# ramanPi_powerControlBoard.net
KiCad netlist of a schematic drawn in EAGLE
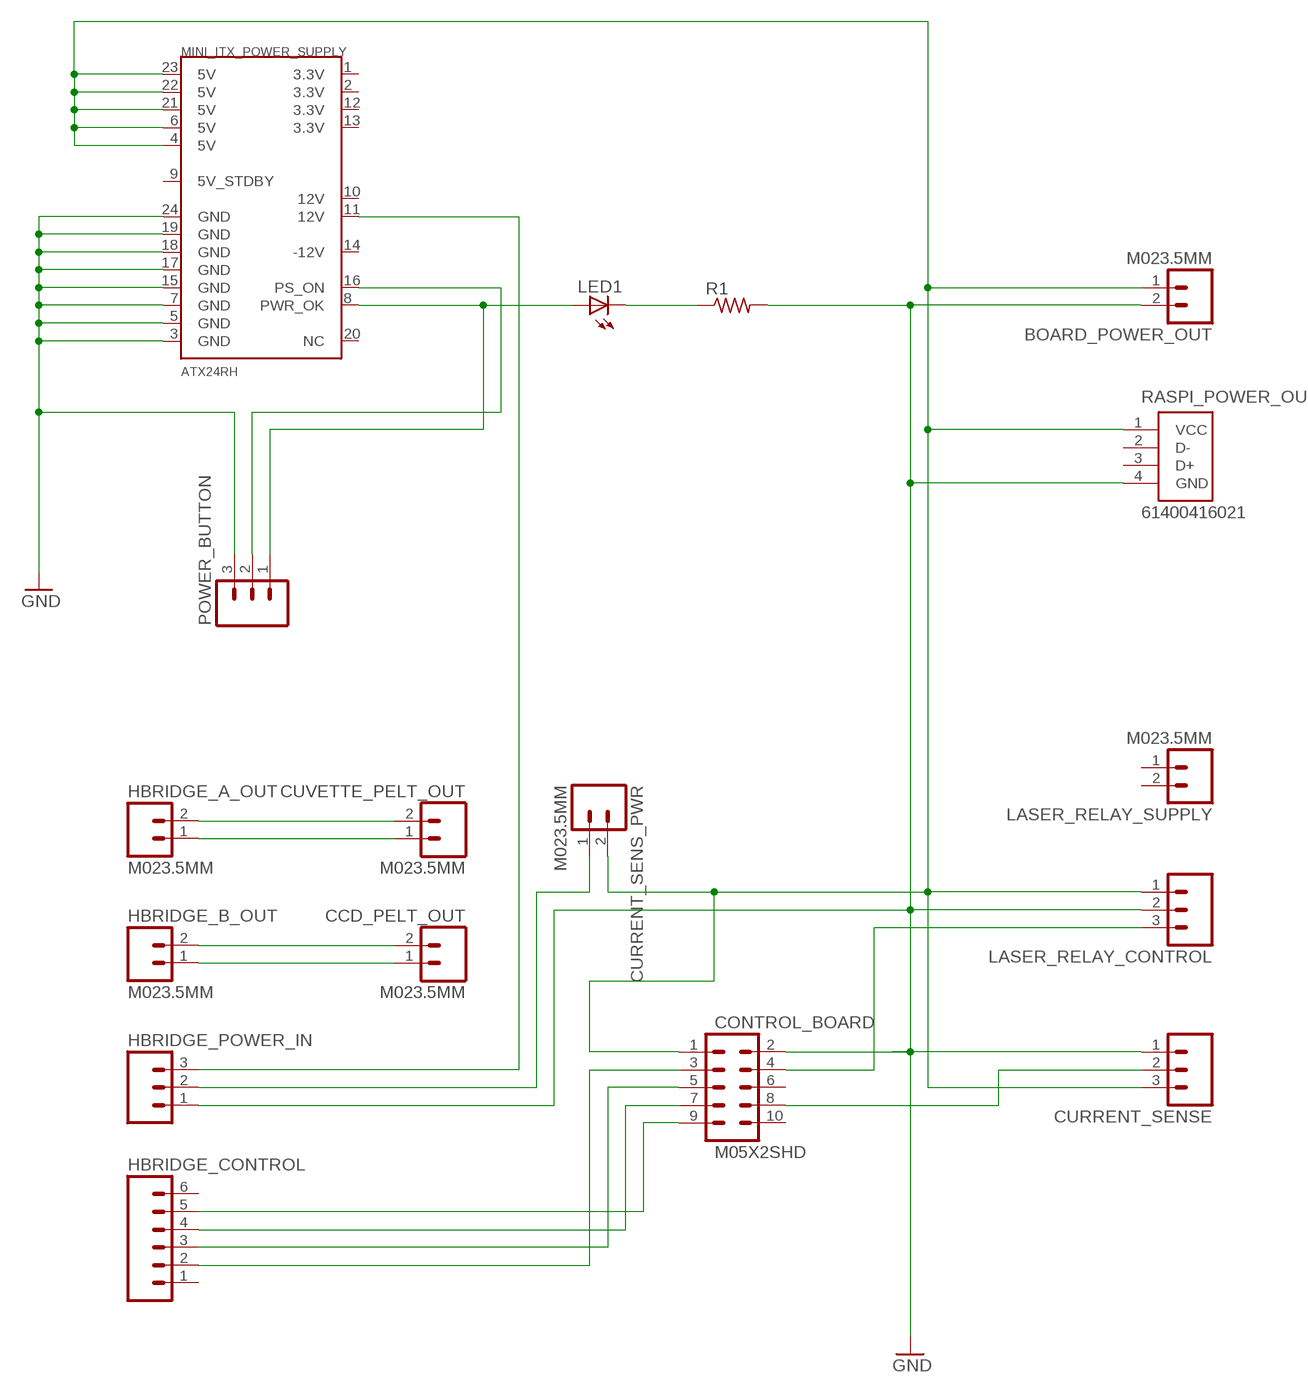
[diagram p0: schematic, sheet 1]

(export (version "E")
  (design (tool "Eeschema 10.0.6"))
  (components
    (comp (ref "BOARD_POWER_OUT")
      (value "M023.5MM")
      (footprint "eagle-import:SCREWTERMINAL-3.5MM-2")
      (libsource (lib "eagle-import") (part "M023.5MM"))
    )
    (comp (ref "CCD_PELT_OUT")
      (value "M023.5MM")
      (footprint "eagle-import:SCREWTERMINAL-3.5MM-2")
      (libsource (lib "eagle-import") (part "M023.5MM"))
    )
    (comp (ref "CONTROL_BOARD")
      (value "M05X2SHD")
      (footprint "eagle-import:2X5-SHROUDED")
      (libsource (lib "eagle-import") (part "M05X2SHD"))
    )
    (comp (ref "CURRENT_SENSE")
      (value "M03PTH")
      (footprint "eagle-import:1X03")
      (libsource (lib "eagle-import") (part "M03PTH"))
    )
    (comp (ref "CURRENT_SENS_PWR")
      (value "M023.5MM")
      (footprint "eagle-import:SCREWTERMINAL-3.5MM-2")
      (libsource (lib "eagle-import") (part "M023.5MM"))
    )
    (comp (ref "CUVETTE_PELT_OUT")
      (value "M023.5MM")
      (footprint "eagle-import:SCREWTERMINAL-3.5MM-2")
      (libsource (lib "eagle-import") (part "M023.5MM"))
    )
    (comp (ref "HBRIDGE_A_OUT")
      (value "M023.5MM")
      (footprint "eagle-import:SCREWTERMINAL-3.5MM-2")
      (libsource (lib "eagle-import") (part "M023.5MM"))
    )
    (comp (ref "HBRIDGE_B_OUT")
      (value "M023.5MM")
      (footprint "eagle-import:SCREWTERMINAL-3.5MM-2")
      (libsource (lib "eagle-import") (part "M023.5MM"))
    )
    (comp (ref "HBRIDGE_CONTROL")
      (value "M06SIP")
      (footprint "eagle-import:1X06")
      (libsource (lib "eagle-import") (part "M06SIP"))
    )
    (comp (ref "HBRIDGE_POWER_IN")
      (value "M03SCREW")
      (footprint "eagle-import:SCREWTERMINAL-3.5MM-3")
      (libsource (lib "eagle-import") (part "M03SCREW"))
    )
    (comp (ref "LASER_RELAY_CONTROL")
      (value "M03PTH")
      (footprint "eagle-import:1X03")
      (libsource (lib "eagle-import") (part "M03PTH"))
    )
    (comp (ref "LASER_RELAY_SUPPLY")
      (value "M023.5MM")
      (footprint "eagle-import:SCREWTERMINAL-3.5MM-2")
      (libsource (lib "eagle-import") (part "M023.5MM"))
    )
    (comp (ref "LED1")
      (value "LED5MM")
      (footprint "eagle-import:LED5MM")
      (libsource (lib "eagle-import") (part "LED5MM"))
    )
    (comp (ref "MINI_ITX_POWER_SUPPLY")
      (value "ATX24RH")
      (footprint "eagle-import:ATX24_RIGHT_ANGLE")
      (libsource (lib "eagle-import") (part "ATX24RH"))
    )
    (comp (ref "POWER_BUTTON")
      (value "M03JST-PTH-VERT")
      (footprint "eagle-import:JST-3-PTH-VERT")
      (libsource (lib "eagle-import") (part "M03JST-PTH-VERT"))
    )
    (comp (ref "R1")
      (value "R-US_M1206")
      (footprint "eagle-import:M1206")
      (libsource (lib "eagle-import") (part "R-US_M1206"))
    )
    (comp (ref "RASPI_POWER_OUT")
      (value "61400416021")
      (footprint "eagle-import:61400416021")
      (libsource (lib "eagle-import") (part "61400416021"))
    )
  )
  (nets
    (net (code "1") (name "GND") (class "Default")
      (node (ref "BOARD_POWER_OUT") (pin "2") (pinfunction "2_2") (pintype "passive"))
      (node (ref "CONTROL_BOARD") (pin "2") (pinfunction "2_2") (pintype "passive"))
      (node (ref "CURRENT_SENSE") (pin "1") (pinfunction "1_1") (pintype "passive"))
      (node (ref "HBRIDGE_POWER_IN") (pin "1") (pinfunction "1_1") (pintype "passive"))
      (node (ref "LASER_RELAY_CONTROL") (pin "2") (pinfunction "2_2") (pintype "passive"))
      (node (ref "MINI_ITX_POWER_SUPPLY") (pin "15") (pinfunction "GND_15") (pintype "bidirectional"))
      (node (ref "MINI_ITX_POWER_SUPPLY") (pin "17") (pinfunction "GND_17") (pintype "bidirectional"))
      (node (ref "MINI_ITX_POWER_SUPPLY") (pin "18") (pinfunction "GND_18") (pintype "bidirectional"))
      (node (ref "MINI_ITX_POWER_SUPPLY") (pin "19") (pinfunction "GND_19") (pintype "bidirectional"))
      (node (ref "MINI_ITX_POWER_SUPPLY") (pin "24") (pinfunction "GND_24") (pintype "bidirectional"))
      (node (ref "MINI_ITX_POWER_SUPPLY") (pin "3") (pinfunction "GND_3") (pintype "bidirectional"))
      (node (ref "MINI_ITX_POWER_SUPPLY") (pin "5") (pinfunction "GND_5") (pintype "bidirectional"))
      (node (ref "MINI_ITX_POWER_SUPPLY") (pin "7") (pinfunction "GND_7") (pintype "bidirectional"))
      (node (ref "POWER_BUTTON") (pin "3") (pinfunction "3_3") (pintype "passive"))
      (node (ref "R1") (pin "2") (pinfunction "2_2") (pintype "passive"))
      (node (ref "RASPI_POWER_OUT") (pin "4") (pinfunction "GND_4") (pintype "passive"))
    )
    (net (code "2") (name "Net-(CCD_PELT_OUT-Pad1)") (class "Default")
      (node (ref "CCD_PELT_OUT") (pin "1") (pinfunction "1_1") (pintype "passive"))
      (node (ref "HBRIDGE_B_OUT") (pin "1") (pinfunction "1_1") (pintype "passive"))
    )
    (net (code "3") (name "Net-(CCD_PELT_OUT-Pad2)") (class "Default")
      (node (ref "CCD_PELT_OUT") (pin "2") (pinfunction "2_2") (pintype "passive"))
      (node (ref "HBRIDGE_B_OUT") (pin "2") (pinfunction "2_2") (pintype "passive"))
    )
    (net (code "4") (name "Net-(CONTROL_BOARD-Pad3)") (class "Default")
      (node (ref "CONTROL_BOARD") (pin "3") (pinfunction "3_3") (pintype "passive"))
      (node (ref "HBRIDGE_CONTROL") (pin "2") (pinfunction "2_2") (pintype "passive"))
    )
    (net (code "5") (name "Net-(CONTROL_BOARD-Pad4)") (class "Default")
      (node (ref "CONTROL_BOARD") (pin "4") (pinfunction "4_4") (pintype "passive"))
      (node (ref "LASER_RELAY_CONTROL") (pin "3") (pinfunction "3_3") (pintype "passive"))
    )
    (net (code "6") (name "Net-(CONTROL_BOARD-Pad5)") (class "Default")
      (node (ref "CONTROL_BOARD") (pin "5") (pinfunction "5_5") (pintype "passive"))
      (node (ref "HBRIDGE_CONTROL") (pin "3") (pinfunction "3_3") (pintype "passive"))
    )
    (net (code "7") (name "Net-(CONTROL_BOARD-Pad7)") (class "Default")
      (node (ref "CONTROL_BOARD") (pin "7") (pinfunction "7_7") (pintype "passive"))
      (node (ref "HBRIDGE_CONTROL") (pin "4") (pinfunction "4_4") (pintype "passive"))
    )
    (net (code "8") (name "Net-(CONTROL_BOARD-Pad8)") (class "Default")
      (node (ref "CONTROL_BOARD") (pin "8") (pinfunction "8_8") (pintype "passive"))
      (node (ref "CURRENT_SENSE") (pin "2") (pinfunction "2_2") (pintype "passive"))
    )
    (net (code "9") (name "Net-(CONTROL_BOARD-Pad9)") (class "Default")
      (node (ref "CONTROL_BOARD") (pin "9") (pinfunction "9_9") (pintype "passive"))
      (node (ref "HBRIDGE_CONTROL") (pin "5") (pinfunction "5_5") (pintype "passive"))
    )
    (net (code "10") (name "Net-(CURRENT_SENS_PWR-Pad1)") (class "Default")
      (node (ref "CURRENT_SENS_PWR") (pin "1") (pinfunction "1_1") (pintype "passive"))
      (node (ref "HBRIDGE_POWER_IN") (pin "2") (pinfunction "2_2") (pintype "passive"))
    )
    (net (code "11") (name "Net-(CUVETTE_PELT_OUT-Pad1)") (class "Default")
      (node (ref "CUVETTE_PELT_OUT") (pin "1") (pinfunction "1_1") (pintype "passive"))
      (node (ref "HBRIDGE_A_OUT") (pin "1") (pinfunction "1_1") (pintype "passive"))
    )
    (net (code "12") (name "Net-(CUVETTE_PELT_OUT-Pad2)") (class "Default")
      (node (ref "CUVETTE_PELT_OUT") (pin "2") (pinfunction "2_2") (pintype "passive"))
      (node (ref "HBRIDGE_A_OUT") (pin "2") (pinfunction "2_2") (pintype "passive"))
    )
    (net (code "13") (name "Net-(HBRIDGE_POWER_IN-Pad3)") (class "Default")
      (node (ref "HBRIDGE_POWER_IN") (pin "3") (pinfunction "3_3") (pintype "passive"))
      (node (ref "MINI_ITX_POWER_SUPPLY") (pin "11") (pinfunction "12V_11") (pintype "bidirectional"))
    )
    (net (code "14") (name "Net-(LED1-C)") (class "Default")
      (node (ref "LED1") (pin "K") (pinfunction "C_K") (pintype "passive"))
      (node (ref "R1") (pin "1") (pinfunction "1_1") (pintype "passive"))
    )
    (net (code "15") (name "Net-(MINI_ITX_POWER_SUPPLY-PS_ON)") (class "Default")
      (node (ref "MINI_ITX_POWER_SUPPLY") (pin "16") (pinfunction "PS_ON_16") (pintype "bidirectional"))
      (node (ref "POWER_BUTTON") (pin "2") (pinfunction "2_2") (pintype "passive"))
    )
    (net (code "16") (name "Net-(MINI_ITX_POWER_SUPPLY-PWR_OK)") (class "Default")
      (node (ref "LED1") (pin "A") (pinfunction "A_A") (pintype "passive"))
      (node (ref "MINI_ITX_POWER_SUPPLY") (pin "8") (pinfunction "PWR_OK_8") (pintype "bidirectional"))
      (node (ref "POWER_BUTTON") (pin "1") (pinfunction "1_1") (pintype "passive"))
    )
    (net (code "17") (name "Net-(RASPI_POWER_OUT-VCC)") (class "Default")
      (node (ref "BOARD_POWER_OUT") (pin "1") (pinfunction "1_1") (pintype "passive"))
      (node (ref "CONTROL_BOARD") (pin "1") (pinfunction "1_1") (pintype "passive"))
      (node (ref "CURRENT_SENSE") (pin "3") (pinfunction "3_3") (pintype "passive"))
      (node (ref "CURRENT_SENS_PWR") (pin "2") (pinfunction "2_2") (pintype "passive"))
      (node (ref "LASER_RELAY_CONTROL") (pin "1") (pinfunction "1_1") (pintype "passive"))
      (node (ref "MINI_ITX_POWER_SUPPLY") (pin "21") (pinfunction "5V_21") (pintype "bidirectional"))
      (node (ref "MINI_ITX_POWER_SUPPLY") (pin "22") (pinfunction "5V_22") (pintype "bidirectional"))
      (node (ref "MINI_ITX_POWER_SUPPLY") (pin "23") (pinfunction "5V_23") (pintype "bidirectional"))
      (node (ref "MINI_ITX_POWER_SUPPLY") (pin "4") (pinfunction "5V_4") (pintype "bidirectional"))
      (node (ref "MINI_ITX_POWER_SUPPLY") (pin "6") (pinfunction "5V_6") (pintype "bidirectional"))
      (node (ref "RASPI_POWER_OUT") (pin "1") (pinfunction "VCC_1") (pintype "passive"))
    )
    (net (code "18") (name "unconnected-(CONTROL_BOARD-Pad6)") (class "Default")
      (node (ref "CONTROL_BOARD") (pin "6") (pinfunction "6_6") (pintype "passive"))
    )
    (net (code "19") (name "unconnected-(CONTROL_BOARD-Pad10)") (class "Default")
      (node (ref "CONTROL_BOARD") (pin "10") (pinfunction "10_10") (pintype "passive"))
    )
    (net (code "20") (name "unconnected-(HBRIDGE_CONTROL-Pad1)") (class "Default")
      (node (ref "HBRIDGE_CONTROL") (pin "1") (pinfunction "1_1") (pintype "passive"))
    )
    (net (code "21") (name "unconnected-(HBRIDGE_CONTROL-Pad6)") (class "Default")
      (node (ref "HBRIDGE_CONTROL") (pin "6") (pinfunction "6_6") (pintype "passive"))
    )
    (net (code "22") (name "unconnected-(LASER_RELAY_SUPPLY-Pad1)") (class "Default")
      (node (ref "LASER_RELAY_SUPPLY") (pin "1") (pinfunction "1_1") (pintype "passive"))
    )
    (net (code "23") (name "unconnected-(LASER_RELAY_SUPPLY-Pad2)") (class "Default")
      (node (ref "LASER_RELAY_SUPPLY") (pin "2") (pinfunction "2_2") (pintype "passive"))
    )
    (net (code "24") (name "unconnected-(MINI_ITX_POWER_SUPPLY--12V-Pad14)") (class "Default")
      (node (ref "MINI_ITX_POWER_SUPPLY") (pin "14") (pinfunction "-12V_14") (pintype "bidirectional"))
    )
    (net (code "25") (name "unconnected-(MINI_ITX_POWER_SUPPLY-3.3V-Pad1)") (class "Default")
      (node (ref "MINI_ITX_POWER_SUPPLY") (pin "1") (pinfunction "3.3V_1") (pintype "bidirectional"))
    )
    (net (code "26") (name "unconnected-(MINI_ITX_POWER_SUPPLY-3.3V-Pad2)") (class "Default")
      (node (ref "MINI_ITX_POWER_SUPPLY") (pin "2") (pinfunction "3.3V_2") (pintype "bidirectional"))
    )
    (net (code "27") (name "unconnected-(MINI_ITX_POWER_SUPPLY-3.3V-Pad12)") (class "Default")
      (node (ref "MINI_ITX_POWER_SUPPLY") (pin "12") (pinfunction "3.3V_12") (pintype "bidirectional"))
    )
    (net (code "28") (name "unconnected-(MINI_ITX_POWER_SUPPLY-3.3V-Pad13)") (class "Default")
      (node (ref "MINI_ITX_POWER_SUPPLY") (pin "13") (pinfunction "3.3V_13") (pintype "bidirectional"))
    )
    (net (code "29") (name "unconnected-(MINI_ITX_POWER_SUPPLY-5V_STDBY-Pad9)") (class "Default")
      (node (ref "MINI_ITX_POWER_SUPPLY") (pin "9") (pinfunction "5V_STDBY_9") (pintype "bidirectional"))
    )
    (net (code "30") (name "unconnected-(MINI_ITX_POWER_SUPPLY-12V-Pad10)") (class "Default")
      (node (ref "MINI_ITX_POWER_SUPPLY") (pin "10") (pinfunction "12V_10") (pintype "bidirectional"))
    )
    (net (code "31") (name "unconnected-(MINI_ITX_POWER_SUPPLY-NC-Pad20)") (class "Default")
      (node (ref "MINI_ITX_POWER_SUPPLY") (pin "20") (pinfunction "NC_20") (pintype "bidirectional"))
    )
    (net (code "32") (name "unconnected-(RASPI_POWER_OUT-D+-Pad3)") (class "Default")
      (node (ref "RASPI_POWER_OUT") (pin "3") (pinfunction "D+_3") (pintype "passive"))
    )
    (net (code "33") (name "unconnected-(RASPI_POWER_OUT-D--Pad2)") (class "Default")
      (node (ref "RASPI_POWER_OUT") (pin "2") (pinfunction "D-_2") (pintype "passive"))
    )
  )
)
